# 2_4_0-.net
KiCad netlist of a schematic drawn in Altium Designer
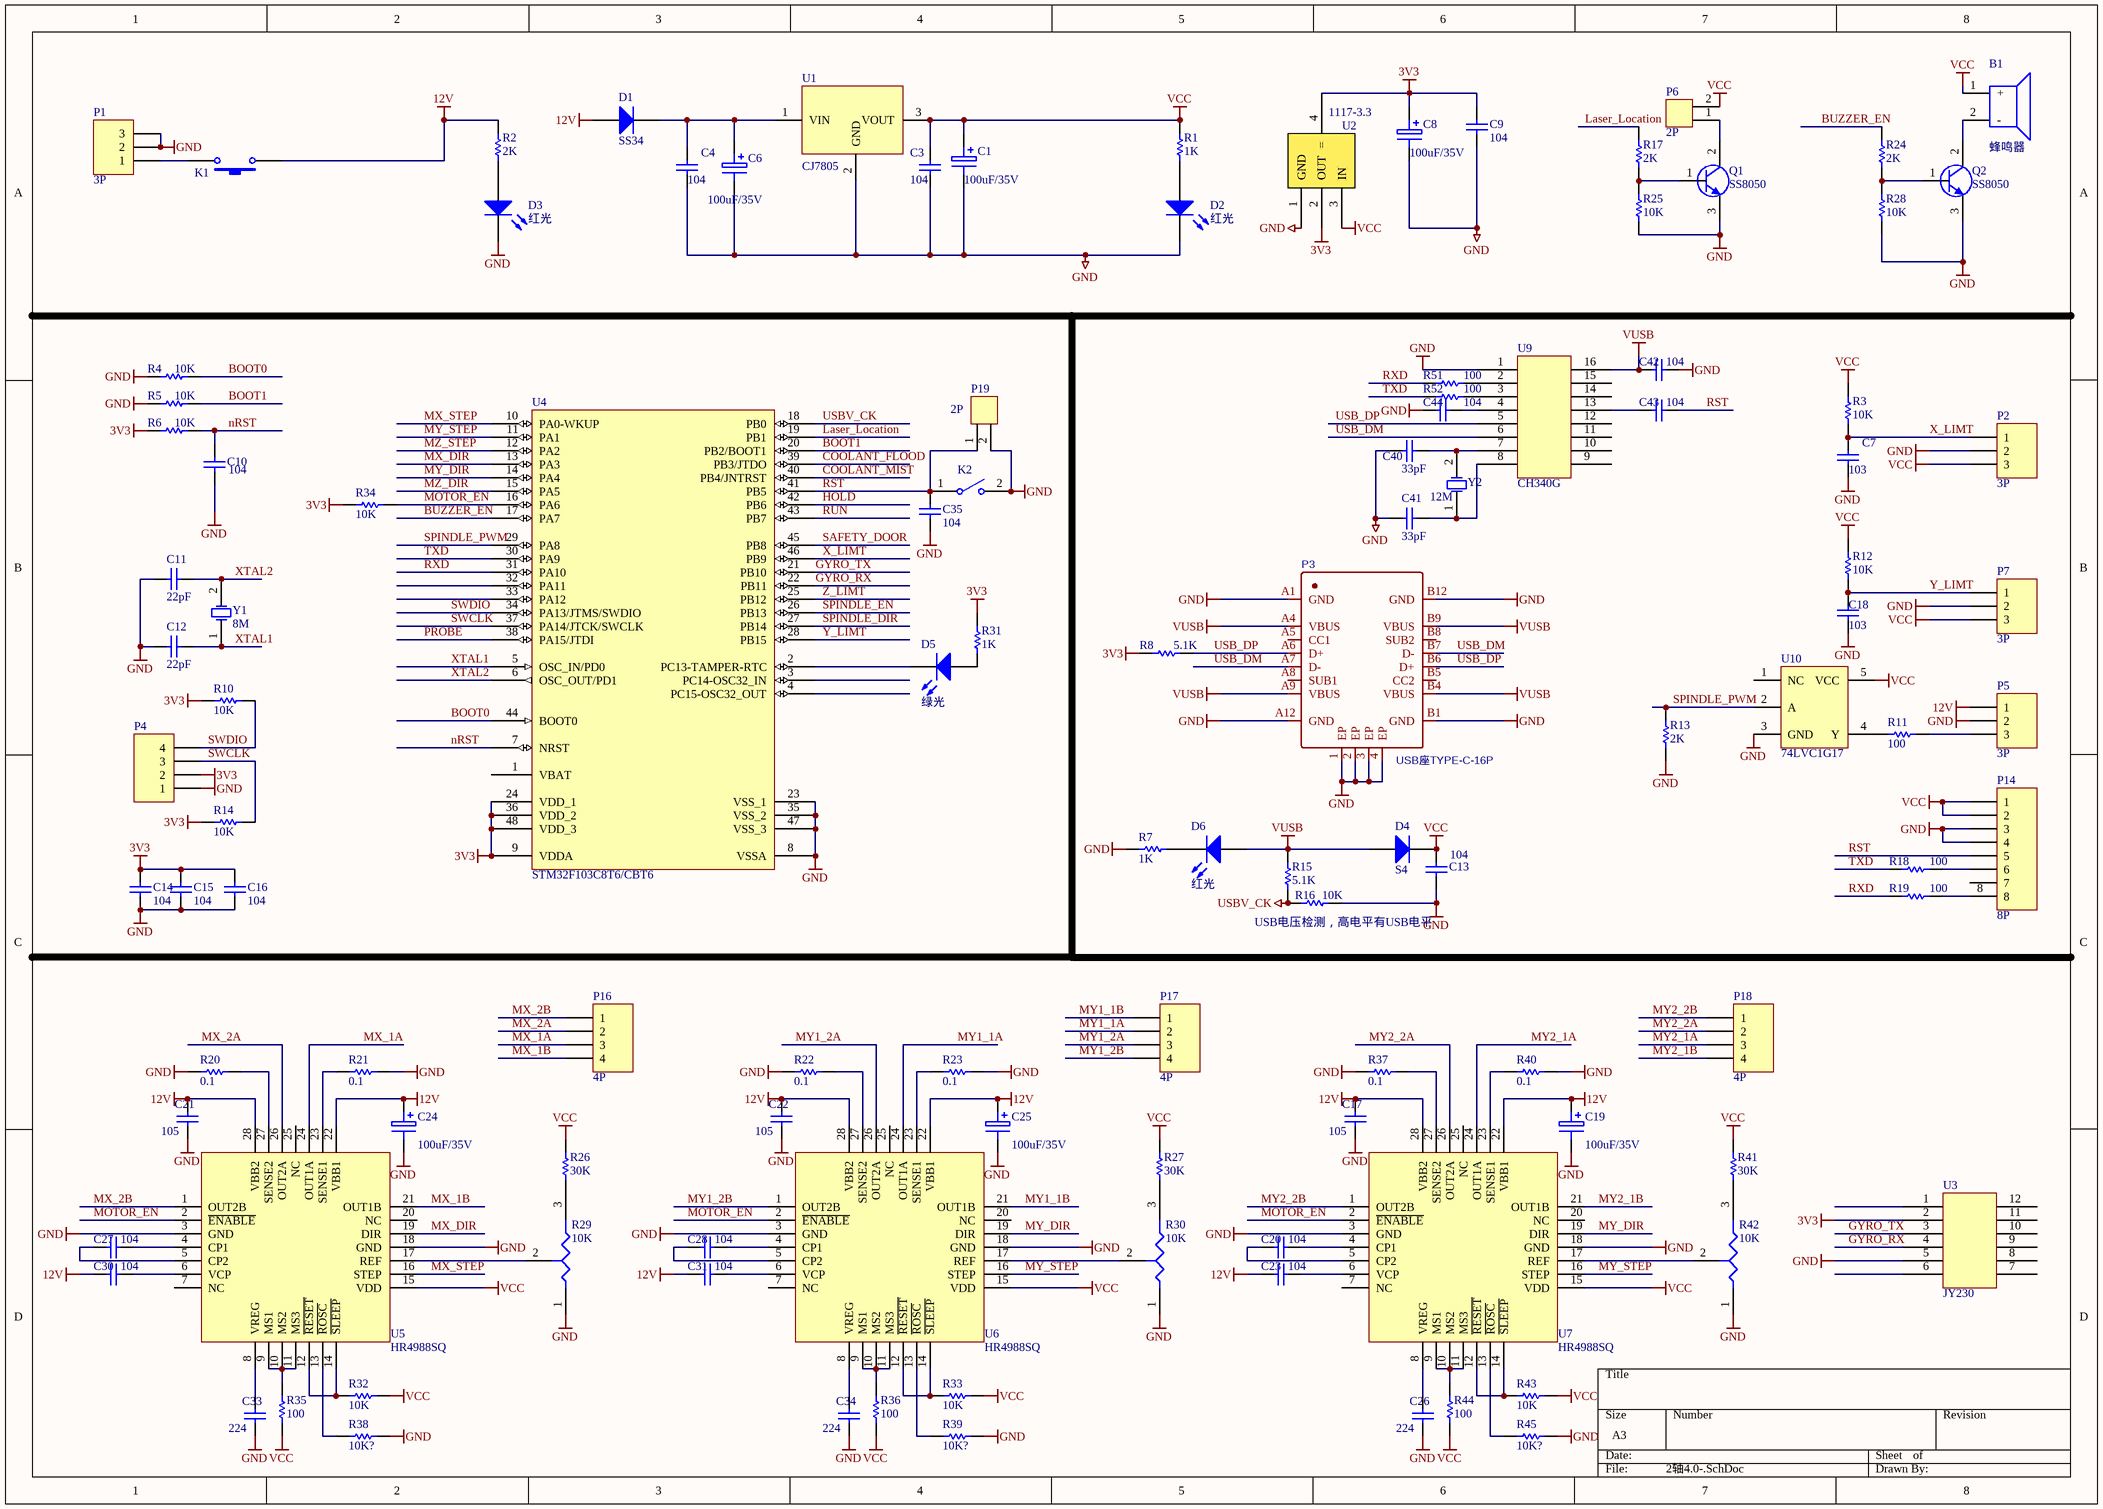
[diagram p0: 2轴4.0-.SchDoc]

(export (version "E")
  (design (tool "Eeschema 10.0.6"))
  (components
    (comp (ref "B1") (value "蜂鸣器") (footprint "蜂鸣器9") (libsource (lib "SCH封装库") (part "蜂鸣器")))
    (comp (ref "C1") (value "100uF/35V") (footprint "电解电容贴片6x6") (libsource (lib "*") (part "ELECTRO1")))
    (comp (ref "C3")
      (value "104")
      (footprint "0603C")
      (description "Capacitor (Semiconductor SIM Model)")
      (fields (field (name "PUBLISHER") "Altium Limited"))
      (libsource (lib "Miscellaneous Devices") (part "Cap Semi"))
    )
    (comp (ref "C4") (value "104") (footprint "0603C") (libsource (lib "SCH封装库") (part "CAP")))
    (comp (ref "C6") (value "100uF/35V") (footprint "电解电容贴片6x6") (libsource (lib "*") (part "ELECTRO1")))
    (comp (ref "C7") (value "103") (footprint "0603C") (libsource (lib "SCH封装库") (part "CAP")))
    (comp (ref "C8") (value "100uF/35V") (footprint "电解电容贴片6x6") (libsource (lib "*") (part "ELECTRO1")))
    (comp (ref "C9")
      (value "104")
      (footprint "0603C")
      (description "Capacitor (Semiconductor SIM Model)")
      (fields (field (name "PUBLISHER") "Altium Limited"))
      (libsource (lib "Miscellaneous Devices") (part "Cap Semi"))
    )
    (comp (ref "C10")
      (value "104")
      (footprint "0603C")
      (description "Capacitor (Semiconductor SIM Model)")
      (fields (field (name "PUBLISHER") "Altium Limited"))
      (libsource (lib "Miscellaneous Devices") (part "Cap Semi"))
    )
    (comp (ref "C11")
      (value "22pF")
      (footprint "0603C")
      (description "Capacitor (Semiconductor SIM Model)")
      (fields (field (name "PUBLISHER") "Altium Limited"))
      (libsource (lib "Miscellaneous Devices") (part "Cap Semi"))
    )
    (comp (ref "C12")
      (value "22pF")
      (footprint "0603C")
      (description "Capacitor (Semiconductor SIM Model)")
      (fields (field (name "PUBLISHER") "Altium Limited"))
      (libsource (lib "Miscellaneous Devices") (part "Cap Semi"))
    )
    (comp (ref "C13")
      (value "104")
      (footprint "0603C")
      (description "Capacitor (Semiconductor SIM Model)")
      (fields (field (name "PUBLISHER") "Altium Limited"))
      (libsource (lib "Miscellaneous Devices") (part "Cap Semi"))
    )
    (comp (ref "C14") (value "104") (footprint "0603C") (libsource (lib "SCH封装库") (part "CAP")))
    (comp (ref "C15") (value "104") (footprint "0603C") (libsource (lib "SCH封装库") (part "CAP")))
    (comp (ref "C16") (value "104") (footprint "0603C") (libsource (lib "SCH封装库") (part "CAP")))
    (comp (ref "C17") (value "105") (footprint "0805C") (libsource (lib "SCH封装库") (part "CAP")))
    (comp (ref "C18") (value "103") (footprint "0603C") (libsource (lib "SCH封装库") (part "CAP")))
    (comp (ref "C19") (value "100uF/35V") (footprint "电解电容贴片6x6") (libsource (lib "*") (part "ELECTRO1")))
    (comp (ref "C20") (value "104") (footprint "0603C") (libsource (lib "SCH封装库") (part "CAP")))
    (comp (ref "C21") (value "105") (footprint "0805C") (libsource (lib "SCH封装库") (part "CAP")))
    (comp (ref "C22") (value "105") (footprint "0805C") (libsource (lib "SCH封装库") (part "CAP")))
    (comp (ref "C23") (value "104") (footprint "0603C") (libsource (lib "SCH封装库") (part "CAP")))
    (comp (ref "C24") (value "100uF/35V") (footprint "电解电容贴片6x6") (libsource (lib "*") (part "ELECTRO1")))
    (comp (ref "C25") (value "100uF/35V") (footprint "电解电容贴片6x6") (libsource (lib "*") (part "ELECTRO1")))
    (comp (ref "C26") (value "224") (footprint "0603C") (libsource (lib "SCH封装库") (part "CAP")))
    (comp (ref "C27") (value "104") (footprint "0603C") (libsource (lib "SCH封装库") (part "CAP")))
    (comp (ref "C28") (value "104") (footprint "0603C") (libsource (lib "SCH封装库") (part "CAP")))
    (comp (ref "C30") (value "104") (footprint "0603C") (libsource (lib "SCH封装库") (part "CAP")))
    (comp (ref "C31") (value "104") (footprint "0603C") (libsource (lib "SCH封装库") (part "CAP")))
    (comp (ref "C33") (value "224") (footprint "0603C") (libsource (lib "SCH封装库") (part "CAP")))
    (comp (ref "C34") (value "224") (footprint "0603C") (libsource (lib "SCH封装库") (part "CAP")))
    (comp (ref "C35")
      (value "104")
      (footprint "0603C")
      (description "Capacitor (Semiconductor SIM Model)")
      (fields (field (name "PUBLISHER") "Altium Limited"))
      (libsource (lib "Miscellaneous Devices") (part "Cap Semi"))
    )
    (comp (ref "C40")
      (value "33pF")
      (footprint "0603C")
      (description "Capacitor (Semiconductor SIM Model)")
      (fields (field (name "PUBLISHER") "Altium Limited"))
      (libsource (lib "Miscellaneous Devices") (part "Cap Semi"))
    )
    (comp (ref "C41")
      (value "33pF")
      (footprint "0603C")
      (description "Capacitor (Semiconductor SIM Model)")
      (fields (field (name "PUBLISHER") "Altium Limited"))
      (libsource (lib "Miscellaneous Devices") (part "Cap Semi"))
    )
    (comp (ref "C42")
      (value "104")
      (footprint "0603C")
      (description "Capacitor (Semiconductor SIM Model)")
      (fields (field (name "PUBLISHER") "Altium Limited"))
      (libsource (lib "Miscellaneous Devices") (part "Cap Semi"))
    )
    (comp (ref "C43")
      (value "104")
      (footprint "0603C")
      (description "Capacitor (Semiconductor SIM Model)")
      (fields (field (name "PUBLISHER") "Altium Limited"))
      (libsource (lib "Miscellaneous Devices") (part "Cap Semi"))
    )
    (comp (ref "C44")
      (value "104")
      (footprint "0603C")
      (description "Capacitor (Semiconductor SIM Model)")
      (fields (field (name "PUBLISHER") "Altium Limited"))
      (libsource (lib "Miscellaneous Devices") (part "Cap Semi"))
    )
    (comp (ref "D1") (value "SS34") (footprint "SMA") (libsource (lib "SCH封装库") (part "1N4148")))
    (comp (ref "D2") (value "红光") (footprint "0603LED") (libsource (lib "SCH封装库") (part "LED")))
    (comp (ref "D3") (value "红光") (footprint "0603LED") (libsource (lib "SCH封装库") (part "LED")))
    (comp (ref "D4") (value "S4") (footprint "SOD-123") (libsource (lib "SCH封装库") (part "1N4148")))
    (comp (ref "D5") (value "绿光") (footprint "0603LED") (libsource (lib "SCH封装库") (part "LED")))
    (comp (ref "D6") (value "红光") (footprint "0603LED") (libsource (lib "SCH封装库") (part "LED")))
    (comp (ref "K1") (value "按键") (footprint "按键18x13") (libsource (lib "SCH封装库") (part "按键")))
    (comp (ref "K2") (value "开关") (footprint "按键6x6贴片") (libsource (lib "SCH封装库") (part "开关")))
    (comp (ref "P1") (value "3P") (footprint "DC0044A") (libsource (lib "") (part "3P_1")))
    (comp (ref "P2") (value "3P") (footprint "HDR1X3_P") (libsource (lib "SCH封装库") (part "3P")))
    (comp (ref "P3")
      (value "USB座TYPE-C-16P")
      (footprint "USB-TYPE-C-16P")
      (fields
        (field (name "BOM_SUPPLIER PART") "C709358")
        (field (name "BOM_MANUFACTURER PART") "KH-TYPE-C-16P-T")
        (field (name "CONTRIBUTOR") "LCSC")
      )
      (libsource (lib "SCH封装库") (part "USB座TYPE-C-16P"))
    )
    (comp (ref "P4") (value "~") (footprint "SIP4") (libsource (lib "") (part "4P_1")))
    (comp (ref "P5") (value "3P") (footprint "HDR1X3_P") (libsource (lib "SCH封装库") (part "3P")))
    (comp (ref "P6") (value "2P") (footprint "HDR1X2_P") (libsource (lib "SCH封装库") (part "2P")))
    (comp (ref "P7") (value "3P") (footprint "HDR1X3_P") (libsource (lib "SCH封装库") (part "3P")))
    (comp (ref "P14") (value "8P") (footprint "IDC8弯脚") (libsource (lib "SCH封装库") (part "8P")))
    (comp (ref "P16") (value "4P") (footprint "HDR1X4_P") (libsource (lib "SCH封装库") (part "4P")))
    (comp (ref "P17") (value "4P") (footprint "HDR1X4_P") (libsource (lib "SCH封装库") (part "4P")))
    (comp (ref "P18") (value "4P") (footprint "HDR1X4_P") (libsource (lib "SCH封装库") (part "4P")))
    (comp (ref "P19") (value "2P") (footprint "HDR1X2_P") (libsource (lib "") (part "2P_1")))
    (comp (ref "Q1")
      (value "SS8050")
      (footprint "SOT-23")
      (fields (field (name "PUBLISHER") "Altium Limited"))
      (libsource (lib "SCH封装库") (part "NPN"))
    )
    (comp (ref "Q2")
      (value "SS8050")
      (footprint "SOT-23")
      (fields (field (name "PUBLISHER") "Altium Limited"))
      (libsource (lib "SCH封装库") (part "NPN"))
    )
    (comp (ref "R1")
      (value "1K")
      (footprint "0603R")
      (description "Resistor")
      (fields (field (name "PUBLISHER") "Altium Limited"))
      (libsource (lib "SCH封装库") (part "RES"))
    )
    (comp (ref "R2")
      (value "2K")
      (footprint "0603R")
      (description "Resistor")
      (fields (field (name "PUBLISHER") "Altium Limited"))
      (libsource (lib "SCH封装库") (part "RES"))
    )
    (comp (ref "R3")
      (value "10K")
      (footprint "0603R")
      (description "Resistor")
      (fields (field (name "PUBLISHER") "Altium Limited"))
      (libsource (lib "SCH封装库") (part "RES"))
    )
    (comp (ref "R4")
      (value "10K")
      (footprint "0603R")
      (description "Resistor")
      (fields (field (name "Comment") "10k") (field (name "PUBLISHER") "Altium Limited"))
      (libsource (lib "SCH封装库") (part "RES"))
    )
    (comp (ref "R5")
      (value "10K")
      (footprint "0603R")
      (description "Resistor")
      (fields (field (name "Comment") "10k") (field (name "PUBLISHER") "Altium Limited"))
      (libsource (lib "SCH封装库") (part "RES"))
    )
    (comp (ref "R6")
      (value "10K")
      (footprint "0603R")
      (description "Resistor")
      (fields (field (name "Comment") "10k") (field (name "PUBLISHER") "Altium Limited"))
      (libsource (lib "SCH封装库") (part "RES"))
    )
    (comp (ref "R7")
      (value "1K")
      (footprint "0603R")
      (description "Resistor")
      (fields (field (name "PUBLISHER") "Altium Limited"))
      (libsource (lib "SCH封装库") (part "RES"))
    )
    (comp (ref "R8")
      (value "5.1K")
      (footprint "0603R")
      (description "Resistor")
      (fields (field (name "PUBLISHER") "Altium Limited"))
      (libsource (lib "SCH封装库") (part "RES"))
    )
    (comp (ref "R10")
      (value "10K")
      (footprint "0603R")
      (description "Resistor")
      (fields (field (name "Comment") "10k") (field (name "PUBLISHER") "Altium Limited"))
      (libsource (lib "SCH封装库") (part "RES"))
    )
    (comp (ref "R11")
      (value "100")
      (footprint "0603R")
      (description "Resistor")
      (fields (field (name "PUBLISHER") "Altium Limited"))
      (libsource (lib "SCH封装库") (part "RES"))
    )
    (comp (ref "R12")
      (value "10K")
      (footprint "0603R")
      (description "Resistor")
      (fields (field (name "PUBLISHER") "Altium Limited"))
      (libsource (lib "SCH封装库") (part "RES"))
    )
    (comp (ref "R13")
      (value "2K")
      (footprint "0603R")
      (description "Resistor")
      (fields (field (name "PUBLISHER") "Altium Limited"))
      (libsource (lib "SCH封装库") (part "RES"))
    )
    (comp (ref "R14")
      (value "10K")
      (footprint "0603R")
      (description "Resistor")
      (fields (field (name "Comment") "10k") (field (name "PUBLISHER") "Altium Limited"))
      (libsource (lib "SCH封装库") (part "RES"))
    )
    (comp (ref "R15")
      (value "5.1K")
      (footprint "0603R")
      (description "Resistor")
      (fields (field (name "PUBLISHER") "Altium Limited"))
      (libsource (lib "SCH封装库") (part "RES"))
    )
    (comp (ref "R16")
      (value "10K")
      (footprint "0603R")
      (description "Resistor")
      (fields (field (name "PUBLISHER") "Altium Limited"))
      (libsource (lib "SCH封装库") (part "RES"))
    )
    (comp (ref "R17")
      (value "2K")
      (footprint "0603R")
      (description "Resistor")
      (fields (field (name "PUBLISHER") "Altium Limited"))
      (libsource (lib "SCH封装库") (part "RES"))
    )
    (comp (ref "R18")
      (value "100")
      (footprint "0603R")
      (description "Resistor")
      (fields (field (name "PUBLISHER") "Altium Limited"))
      (libsource (lib "SCH封装库") (part "RES"))
    )
    (comp (ref "R19")
      (value "100")
      (footprint "0603R")
      (description "Resistor")
      (fields (field (name "PUBLISHER") "Altium Limited"))
      (libsource (lib "SCH封装库") (part "RES"))
    )
    (comp (ref "R20")
      (value "0.1")
      (footprint "0805R")
      (description "Resistor")
      (fields (field (name "PUBLISHER") "Altium Limited"))
      (libsource (lib "SCH封装库") (part "RES"))
    )
    (comp (ref "R21")
      (value "0.1")
      (footprint "0805R")
      (description "Resistor")
      (fields (field (name "PUBLISHER") "Altium Limited"))
      (libsource (lib "SCH封装库") (part "RES"))
    )
    (comp (ref "R22")
      (value "0.1")
      (footprint "0805R")
      (description "Resistor")
      (fields (field (name "PUBLISHER") "Altium Limited"))
      (libsource (lib "SCH封装库") (part "RES"))
    )
    (comp (ref "R23")
      (value "0.1")
      (footprint "0805R")
      (description "Resistor")
      (fields (field (name "PUBLISHER") "Altium Limited"))
      (libsource (lib "SCH封装库") (part "RES"))
    )
    (comp (ref "R24")
      (value "2K")
      (footprint "0603R")
      (description "Resistor")
      (fields (field (name "PUBLISHER") "Altium Limited"))
      (libsource (lib "SCH封装库") (part "RES"))
    )
    (comp (ref "R25")
      (value "10K")
      (footprint "0603R")
      (description "Resistor")
      (fields (field (name "PUBLISHER") "Altium Limited"))
      (libsource (lib "SCH封装库") (part "RES"))
    )
    (comp (ref "R26")
      (value "30K")
      (footprint "0603R")
      (description "Resistor")
      (fields (field (name "PUBLISHER") "Altium Limited"))
      (libsource (lib "SCH封装库") (part "RES"))
    )
    (comp (ref "R27")
      (value "30K")
      (footprint "0603R")
      (description "Resistor")
      (fields (field (name "PUBLISHER") "Altium Limited"))
      (libsource (lib "SCH封装库") (part "RES"))
    )
    (comp (ref "R28")
      (value "10K")
      (footprint "0603R")
      (description "Resistor")
      (fields (field (name "PUBLISHER") "Altium Limited"))
      (libsource (lib "SCH封装库") (part "RES"))
    )
    (comp (ref "R29") (value "10K") (footprint "松下贴片电位器3x3") (libsource (lib "SCH封装库") (part "电位器")))
    (comp (ref "R30") (value "10K") (footprint "松下贴片电位器3x3") (libsource (lib "SCH封装库") (part "电位器")))
    (comp (ref "R31")
      (value "1K")
      (footprint "0603R")
      (description "Resistor")
      (fields (field (name "PUBLISHER") "Altium Limited"))
      (libsource (lib "SCH封装库") (part "RES"))
    )
    (comp (ref "R32")
      (value "10K")
      (footprint "0603R")
      (description "Resistor")
      (fields (field (name "PUBLISHER") "Altium Limited"))
      (libsource (lib "SCH封装库") (part "RES"))
    )
    (comp (ref "R33")
      (value "10K")
      (footprint "0603R")
      (description "Resistor")
      (fields (field (name "PUBLISHER") "Altium Limited"))
      (libsource (lib "SCH封装库") (part "RES"))
    )
    (comp (ref "R34")
      (value "10K")
      (footprint "0603R")
      (description "Resistor")
      (fields (field (name "PUBLISHER") "Altium Limited"))
      (libsource (lib "SCH封装库") (part "RES"))
    )
    (comp (ref "R35")
      (value "100")
      (footprint "0603R")
      (description "Resistor")
      (fields (field (name "PUBLISHER") "Altium Limited"))
      (libsource (lib "SCH封装库") (part "RES"))
    )
    (comp (ref "R36")
      (value "100")
      (footprint "0603R")
      (description "Resistor")
      (fields (field (name "PUBLISHER") "Altium Limited"))
      (libsource (lib "SCH封装库") (part "RES"))
    )
    (comp (ref "R37")
      (value "0.1")
      (footprint "0805R")
      (description "Resistor")
      (fields (field (name "PUBLISHER") "Altium Limited"))
      (libsource (lib "SCH封装库") (part "RES"))
    )
    (comp (ref "R38")
      (value "10K?")
      (footprint "0603R")
      (description "Resistor")
      (fields (field (name "PUBLISHER") "Altium Limited"))
      (libsource (lib "SCH封装库") (part "RES"))
    )
    (comp (ref "R39")
      (value "10K?")
      (footprint "0603R")
      (description "Resistor")
      (fields (field (name "PUBLISHER") "Altium Limited"))
      (libsource (lib "SCH封装库") (part "RES"))
    )
    (comp (ref "R40")
      (value "0.1")
      (footprint "0805R")
      (description "Resistor")
      (fields (field (name "PUBLISHER") "Altium Limited"))
      (libsource (lib "SCH封装库") (part "RES"))
    )
    (comp (ref "R41")
      (value "30K")
      (footprint "0603R")
      (description "Resistor")
      (fields (field (name "PUBLISHER") "Altium Limited"))
      (libsource (lib "SCH封装库") (part "RES"))
    )
    (comp (ref "R42") (value "10K") (footprint "松下贴片电位器3x3") (libsource (lib "SCH封装库") (part "电位器")))
    (comp (ref "R43")
      (value "10K")
      (footprint "0603R")
      (description "Resistor")
      (fields (field (name "PUBLISHER") "Altium Limited"))
      (libsource (lib "SCH封装库") (part "RES"))
    )
    (comp (ref "R44")
      (value "100")
      (footprint "0603R")
      (description "Resistor")
      (fields (field (name "PUBLISHER") "Altium Limited"))
      (libsource (lib "SCH封装库") (part "RES"))
    )
    (comp (ref "R45")
      (value "10K?")
      (footprint "0603R")
      (description "Resistor")
      (fields (field (name "PUBLISHER") "Altium Limited"))
      (libsource (lib "SCH封装库") (part "RES"))
    )
    (comp (ref "R51")
      (value "100")
      (footprint "0603R")
      (description "Resistor")
      (fields (field (name "PUBLISHER") "Altium Limited"))
      (libsource (lib "SCH封装库") (part "RES"))
    )
    (comp (ref "R52")
      (value "100")
      (footprint "0603R")
      (description "Resistor")
      (fields (field (name "PUBLISHER") "Altium Limited"))
      (libsource (lib "SCH封装库") (part "RES"))
    )
    (comp (ref "U1") (value "CJ7805") (footprint "TO-263-2") (libsource (lib "SCH封装库") (part "7805")))
    (comp (ref "U2") (value "1117-3.3") (footprint "SOT-223") (libsource (lib "Party600") (part "LM1117")))
    (comp (ref "U3") (value "JY230") (footprint "舵螺仪JY-230") (libsource (lib "SCH封装库") (part "DIP12")))
    (comp (ref "U4")
      (value "STM32F103C8T6/CBT6")
      (footprint "LQFP48")
      (description "STM32 ARM-based 32-bit MCU with 32 Kbytes Flash, 48-pin LQFP, Industrial Temperature")
      (fields (field (name "PUBLISHER") "*"))
      (libsource (lib "ST Microcontroller 32-Bit STM32 SCH") (part "STM32F103C6T6"))
    )
    (comp (ref "U5") (value "HR4988SQ") (footprint "QFN28") (libsource (lib "SCH封装库") (part "HR4988")))
    (comp (ref "U6") (value "HR4988SQ") (footprint "QFN28") (libsource (lib "SCH封装库") (part "HR4988")))
    (comp (ref "U7") (value "HR4988SQ") (footprint "QFN28") (libsource (lib "SCH封装库") (part "HR4988")))
    (comp (ref "U9") (value "CH340G") (footprint "SOP16") (libsource (lib "SCH封装库") (part "DIP16")))
    (comp (ref "U10")
      (value "74LVC1G17")
      (footprint "SOT-23-5")
      (libsource (lib "SCH封装库") (part "74LVC1G17"))
    )
    (comp (ref "Y1")
      (value "8M")
      (footprint "晶振贴片")
      (description "Crystal Oscillator")
      (fields (field (name "PUBLISHER") "Altium Limited"))
      (libsource (lib "Miscellaneous Devices") (part "XTAL"))
    )
    (comp (ref "Y2")
      (value "12M")
      (footprint "晶振贴片49SSMD")
      (description "Crystal Oscillator")
      (fields (field (name "PUBLISHER") "Altium Limited"))
      (libsource (lib "Miscellaneous Devices") (part "XTAL"))
    )
  )
  (nets
    (net (code "1") (name "/BOOT0") (class "Default")
      (node (ref "R4") (pin "2") (pinfunction "2_2") (pintype "passive"))
      (node (ref "U4") (pin "44") (pinfunction "BOOT0_44") (pintype "input"))
    )
    (net (code "2") (name "/BOOT1") (class "Default")
      (node (ref "R5") (pin "2") (pinfunction "2_2") (pintype "passive"))
      (node (ref "U4") (pin "20") (pinfunction "PB2/BOOT1_20") (pintype "bidirectional"))
    )
    (net (code "3") (name "/BUZZER_EN") (class "Default")
      (node (ref "R24") (pin "1") (pinfunction "1_1") (pintype "passive"))
      (node (ref "U4") (pin "17") (pinfunction "PA7_17") (pintype "bidirectional"))
    )
    (net (code "4") (name "/COOLANT_FLOOD") (class "Default")
      (node (ref "U4") (pin "39") (pinfunction "PB3/JTDO_39") (pintype "bidirectional"))
    )
    (net (code "5") (name "/COOLANT_MIST") (class "Default")
      (node (ref "U4") (pin "40") (pinfunction "PB4/JNTRST_40") (pintype "bidirectional"))
    )
    (net (code "6") (name "/GYRO_RX") (class "Default")
      (node (ref "U3") (pin "4") (pinfunction "4_4") (pintype "passive"))
      (node (ref "U4") (pin "22") (pinfunction "PB11_22") (pintype "bidirectional"))
    )
    (net (code "7") (name "/GYRO_TX") (class "Default")
      (node (ref "U3") (pin "3") (pinfunction "3_3") (pintype "passive"))
      (node (ref "U4") (pin "21") (pinfunction "PB10_21") (pintype "bidirectional"))
    )
    (net (code "8") (name "/HOLD") (class "Default")
      (node (ref "U4") (pin "42") (pinfunction "PB6_42") (pintype "bidirectional"))
    )
    (net (code "9") (name "/Laser_Location") (class "Default")
      (node (ref "R17") (pin "1") (pinfunction "1_1") (pintype "passive"))
      (node (ref "U4") (pin "19") (pinfunction "PB1_19") (pintype "bidirectional"))
    )
    (net (code "10") (name "/MOTOR_EN") (class "Default")
      (node (ref "R34") (pin "1") (pinfunction "1_1") (pintype "passive"))
      (node (ref "U4") (pin "16") (pinfunction "PA6_16") (pintype "bidirectional"))
      (node (ref "U5") (pin "2") (pinfunction "~{ENABLE}_2") (pintype "passive"))
      (node (ref "U6") (pin "2") (pinfunction "~{ENABLE}_2") (pintype "passive"))
      (node (ref "U7") (pin "2") (pinfunction "~{ENABLE}_2") (pintype "passive"))
    )
    (net (code "11") (name "/MX_1A") (class "Default")
      (node (ref "P16") (pin "3") (pinfunction "3_3") (pintype "passive"))
      (node (ref "U5") (pin "24") (pinfunction "OUT1A_24") (pintype "passive"))
    )
    (net (code "12") (name "/MX_1B") (class "Default")
      (node (ref "P16") (pin "4") (pinfunction "4_4") (pintype "passive"))
      (node (ref "U5") (pin "21") (pinfunction "OUT1B_21") (pintype "passive"))
    )
    (net (code "13") (name "/MX_2A") (class "Default")
      (node (ref "P16") (pin "2") (pinfunction "2_2") (pintype "passive"))
      (node (ref "U5") (pin "26") (pinfunction "OUT2A_26") (pintype "passive"))
    )
    (net (code "14") (name "/MX_2B") (class "Default")
      (node (ref "P16") (pin "1") (pinfunction "1_1") (pintype "passive"))
      (node (ref "U5") (pin "1") (pinfunction "OUT2B_1") (pintype "passive"))
    )
    (net (code "15") (name "/MX_DIR") (class "Default")
      (node (ref "U4") (pin "13") (pinfunction "PA3_13") (pintype "bidirectional"))
      (node (ref "U5") (pin "19") (pinfunction "DIR_19") (pintype "passive"))
    )
    (net (code "16") (name "/MX_STEP") (class "Default")
      (node (ref "U4") (pin "10") (pinfunction "PA0-WKUP_10") (pintype "bidirectional"))
      (node (ref "U5") (pin "16") (pinfunction "STEP_16") (pintype "passive"))
    )
    (net (code "17") (name "/MY1_1A") (class "Default")
      (node (ref "P17") (pin "2") (pinfunction "2_2") (pintype "passive"))
      (node (ref "U6") (pin "24") (pinfunction "OUT1A_24") (pintype "passive"))
    )
    (net (code "18") (name "/MY1_1B") (class "Default")
      (node (ref "P17") (pin "1") (pinfunction "1_1") (pintype "passive"))
      (node (ref "U6") (pin "21") (pinfunction "OUT1B_21") (pintype "passive"))
    )
    (net (code "19") (name "/MY1_2A") (class "Default")
      (node (ref "P17") (pin "3") (pinfunction "3_3") (pintype "passive"))
      (node (ref "U6") (pin "26") (pinfunction "OUT2A_26") (pintype "passive"))
    )
    (net (code "20") (name "/MY1_2B") (class "Default")
      (node (ref "P17") (pin "4") (pinfunction "4_4") (pintype "passive"))
      (node (ref "U6") (pin "1") (pinfunction "OUT2B_1") (pintype "passive"))
    )
    (net (code "21") (name "/MY2_1A") (class "Default")
      (node (ref "P18") (pin "3") (pinfunction "3_3") (pintype "passive"))
      (node (ref "U7") (pin "24") (pinfunction "OUT1A_24") (pintype "passive"))
    )
    (net (code "22") (name "/MY2_1B") (class "Default")
      (node (ref "P18") (pin "4") (pinfunction "4_4") (pintype "passive"))
      (node (ref "U7") (pin "21") (pinfunction "OUT1B_21") (pintype "passive"))
    )
    (net (code "23") (name "/MY2_2A") (class "Default")
      (node (ref "P18") (pin "2") (pinfunction "2_2") (pintype "passive"))
      (node (ref "U7") (pin "26") (pinfunction "OUT2A_26") (pintype "passive"))
    )
    (net (code "24") (name "/MY2_2B") (class "Default")
      (node (ref "P18") (pin "1") (pinfunction "1_1") (pintype "passive"))
      (node (ref "U7") (pin "1") (pinfunction "OUT2B_1") (pintype "passive"))
    )
    (net (code "25") (name "/MY_DIR") (class "Default")
      (node (ref "U4") (pin "14") (pinfunction "PA4_14") (pintype "bidirectional"))
      (node (ref "U6") (pin "19") (pinfunction "DIR_19") (pintype "passive"))
      (node (ref "U7") (pin "19") (pinfunction "DIR_19") (pintype "passive"))
    )
    (net (code "26") (name "/MY_STEP") (class "Default")
      (node (ref "U4") (pin "11") (pinfunction "PA1_11") (pintype "bidirectional"))
      (node (ref "U6") (pin "16") (pinfunction "STEP_16") (pintype "passive"))
      (node (ref "U7") (pin "16") (pinfunction "STEP_16") (pintype "passive"))
    )
    (net (code "27") (name "/MZ_DIR") (class "Default")
      (node (ref "U4") (pin "15") (pinfunction "PA5_15") (pintype "bidirectional"))
    )
    (net (code "28") (name "/MZ_STEP") (class "Default")
      (node (ref "U4") (pin "12") (pinfunction "PA2_12") (pintype "bidirectional"))
    )
    (net (code "29") (name "/PROBE") (class "Default")
      (node (ref "U4") (pin "38") (pinfunction "PA15/JTDI_38") (pintype "bidirectional"))
    )
    (net (code "30") (name "/RST") (class "Default")
      (node (ref "C35") (pin "1") (pinfunction "1_1") (pintype "passive"))
      (node (ref "C43") (pin "2") (pinfunction "2_2") (pintype "passive"))
      (node (ref "K2") (pin "1") (pinfunction "COMMON_1") (pintype "passive"))
      (node (ref "P14") (pin "5") (pinfunction "5_5") (pintype "passive"))
      (node (ref "P19") (pin "1") (pintype "passive"))
      (node (ref "U4") (pin "41") (pinfunction "PB5_41") (pintype "bidirectional"))
    )
    (net (code "31") (name "/RUN") (class "Default")
      (node (ref "U4") (pin "43") (pinfunction "PB7_43") (pintype "bidirectional"))
    )
    (net (code "32") (name "/RXD") (class "Default")
      (node (ref "R19") (pin "1") (pinfunction "1_1") (pintype "passive"))
      (node (ref "R51") (pin "2") (pinfunction "2_2") (pintype "passive"))
      (node (ref "U4") (pin "31") (pinfunction "PA10_31") (pintype "bidirectional"))
    )
    (net (code "33") (name "/SAFETY_DOOR") (class "Default")
      (node (ref "U4") (pin "45") (pinfunction "PB8_45") (pintype "bidirectional"))
    )
    (net (code "34") (name "/SPINDLE_DIR") (class "Default")
      (node (ref "U4") (pin "27") (pinfunction "PB14_27") (pintype "bidirectional"))
    )
    (net (code "35") (name "/SPINDLE_EN") (class "Default")
      (node (ref "U4") (pin "26") (pinfunction "PB13_26") (pintype "bidirectional"))
    )
    (net (code "36") (name "/SPINDLE_PWM") (class "Default")
      (node (ref "R13") (pin "2") (pinfunction "2_2") (pintype "passive"))
      (node (ref "U10") (pin "2") (pinfunction "A_2") (pintype "passive"))
      (node (ref "U4") (pin "29") (pinfunction "PA8_29") (pintype "bidirectional"))
    )
    (net (code "37") (name "/SWCLK") (class "Default")
      (node (ref "P4") (pin "3") (pinfunction "3_3") (pintype "passive"))
      (node (ref "R14") (pin "1") (pinfunction "1_1") (pintype "passive"))
      (node (ref "U4") (pin "37") (pinfunction "PA14/JTCK/SWCLK_37") (pintype "bidirectional"))
    )
    (net (code "38") (name "/SWDIO") (class "Default")
      (node (ref "P4") (pin "4") (pinfunction "4_4") (pintype "passive"))
      (node (ref "R10") (pin "1") (pinfunction "1_1") (pintype "passive"))
      (node (ref "U4") (pin "34") (pinfunction "PA13/JTMS/SWDIO_34") (pintype "bidirectional"))
    )
    (net (code "39") (name "/TXD") (class "Default")
      (node (ref "R18") (pin "1") (pinfunction "1_1") (pintype "passive"))
      (node (ref "R52") (pin "2") (pinfunction "2_2") (pintype "passive"))
      (node (ref "U4") (pin "30") (pinfunction "PA9_30") (pintype "bidirectional"))
    )
    (net (code "40") (name "/USB_DM") (class "Default")
      (node (ref "P3") (pin "A7") (pinfunction "D-_A7") (pintype "passive"))
      (node (ref "P3") (pin "B7") (pinfunction "D-_B7") (pintype "passive"))
      (node (ref "U9") (pin "6") (pinfunction "6_6") (pintype "passive"))
    )
    (net (code "41") (name "/USB_DP") (class "Default")
      (node (ref "P3") (pin "A6") (pinfunction "D+_A6") (pintype "passive"))
      (node (ref "P3") (pin "B6") (pinfunction "D+_B6") (pintype "passive"))
      (node (ref "R8") (pin "2") (pinfunction "2_2") (pintype "passive"))
      (node (ref "U9") (pin "5") (pinfunction "5_5") (pintype "passive"))
    )
    (net (code "42") (name "/XTAL1") (class "Default")
      (node (ref "C12") (pin "1") (pinfunction "1_1") (pintype "passive"))
      (node (ref "U4") (pin "5") (pinfunction "OSC_IN/PD0_5") (pintype "input"))
      (node (ref "Y1") (pin "1") (pinfunction "OSC1_1") (pintype "passive"))
    )
    (net (code "43") (name "/XTAL2") (class "Default")
      (node (ref "C11") (pin "1") (pinfunction "1_1") (pintype "passive"))
      (node (ref "U4") (pin "6") (pinfunction "OSC_OUT/PD1_6") (pintype "output"))
      (node (ref "Y1") (pin "2") (pinfunction "OSC2_2") (pintype "passive"))
    )
    (net (code "44") (name "/X_LIMT") (class "Default")
      (node (ref "C7") (pin "2") (pinfunction "2_2") (pintype "passive"))
      (node (ref "P2") (pin "1") (pinfunction "1_1") (pintype "passive"))
      (node (ref "R3") (pin "1") (pinfunction "1_1") (pintype "passive"))
      (node (ref "U4") (pin "46") (pinfunction "PB9_46") (pintype "bidirectional"))
    )
    (net (code "45") (name "/Y_LIMT") (class "Default")
      (node (ref "C18") (pin "2") (pinfunction "2_2") (pintype "passive"))
      (node (ref "P7") (pin "1") (pinfunction "1_1") (pintype "passive"))
      (node (ref "R12") (pin "1") (pinfunction "1_1") (pintype "passive"))
      (node (ref "U4") (pin "28") (pinfunction "PB15_28") (pintype "bidirectional"))
    )
    (net (code "46") (name "/Z_LIMT") (class "Default")
      (node (ref "U4") (pin "25") (pinfunction "PB12_25") (pintype "bidirectional"))
    )
    (net (code "47") (name "/nRST") (class "Default")
      (node (ref "C10") (pin "2") (pinfunction "2_2") (pintype "passive"))
      (node (ref "R6") (pin "2") (pinfunction "2_2") (pintype "passive"))
      (node (ref "U4") (pin "7") (pinfunction "NRST_7") (pintype "bidirectional"))
    )
    (net (code "48") (name "3V3") (class "Default")
      (node (ref "C14") (pin "2") (pinfunction "2_2") (pintype "passive"))
      (node (ref "C15") (pin "2") (pinfunction "2_2") (pintype "passive"))
      (node (ref "C16") (pin "2") (pinfunction "2_2") (pintype "passive"))
      (node (ref "C8") (pin "1") (pintype "passive"))
      (node (ref "C9") (pin "2") (pinfunction "2_2") (pintype "passive"))
      (node (ref "P4") (pin "2") (pinfunction "2_2") (pintype "passive"))
      (node (ref "R10") (pin "2") (pinfunction "2_2") (pintype "passive"))
      (node (ref "R14") (pin "2") (pinfunction "2_2") (pintype "passive"))
      (node (ref "R31") (pin "2") (pinfunction "2_2") (pintype "passive"))
      (node (ref "R34") (pin "2") (pinfunction "2_2") (pintype "passive"))
      (node (ref "R6") (pin "1") (pinfunction "1_1") (pintype "passive"))
      (node (ref "R8") (pin "1") (pinfunction "1_1") (pintype "passive"))
      (node (ref "U2") (pin "2") (pinfunction "OUT_2") (pintype "power_in"))
      (node (ref "U2") (pin "4") (pinfunction "=_4") (pintype "power_in"))
      (node (ref "U3") (pin "2") (pinfunction "2_2") (pintype "passive"))
      (node (ref "U4") (pin "24") (pinfunction "VDD_1_24") (pintype "power_in"))
      (node (ref "U4") (pin "36") (pinfunction "VDD_2_36") (pintype "power_in"))
      (node (ref "U4") (pin "48") (pinfunction "VDD_3_48") (pintype "power_in"))
      (node (ref "U4") (pin "9") (pinfunction "VDDA_9") (pintype "power_in"))
    )
    (net (code "49") (name "12V") (class "Default")
      (node (ref "C17") (pin "1") (pinfunction "1_1") (pintype "passive"))
      (node (ref "C19") (pin "1") (pintype "passive"))
      (node (ref "C21") (pin "1") (pinfunction "1_1") (pintype "passive"))
      (node (ref "C22") (pin "1") (pinfunction "1_1") (pintype "passive"))
      (node (ref "C23") (pin "2") (pinfunction "2_2") (pintype "passive"))
      (node (ref "C24") (pin "1") (pintype "passive"))
      (node (ref "C25") (pin "1") (pintype "passive"))
      (node (ref "C30") (pin "2") (pinfunction "2_2") (pintype "passive"))
      (node (ref "C31") (pin "2") (pinfunction "2_2") (pintype "passive"))
      (node (ref "D1") (pin "1") (pinfunction "1_1") (pintype "passive"))
      (node (ref "K1") (pin "1") (pinfunction "1_1") (pintype "passive"))
      (node (ref "P5") (pin "1") (pinfunction "1_1") (pintype "passive"))
      (node (ref "R2") (pin "1") (pinfunction "1_1") (pintype "passive"))
      (node (ref "U5") (pin "22") (pinfunction "VBB1_22") (pintype "passive"))
      (node (ref "U5") (pin "28") (pinfunction "VBB2_28") (pintype "passive"))
      (node (ref "U6") (pin "22") (pinfunction "VBB1_22") (pintype "passive"))
      (node (ref "U6") (pin "28") (pinfunction "VBB2_28") (pintype "passive"))
      (node (ref "U7") (pin "22") (pinfunction "VBB1_22") (pintype "passive"))
      (node (ref "U7") (pin "28") (pinfunction "VBB2_28") (pintype "passive"))
    )
    (net (code "50") (name "GND") (class "Default")
      (node (ref "C1") (pin "2") (pintype "passive"))
      (node (ref "C10") (pin "1") (pinfunction "1_1") (pintype "passive"))
      (node (ref "C11") (pin "2") (pinfunction "2_2") (pintype "passive"))
      (node (ref "C12") (pin "2") (pinfunction "2_2") (pintype "passive"))
      (node (ref "C13") (pin "1") (pinfunction "1_1") (pintype "passive"))
      (node (ref "C14") (pin "1") (pinfunction "1_1") (pintype "passive"))
      (node (ref "C15") (pin "1") (pinfunction "1_1") (pintype "passive"))
      (node (ref "C16") (pin "1") (pinfunction "1_1") (pintype "passive"))
      (node (ref "C17") (pin "2") (pinfunction "2_2") (pintype "passive"))
      (node (ref "C18") (pin "1") (pinfunction "1_1") (pintype "passive"))
      (node (ref "C19") (pin "2") (pintype "passive"))
      (node (ref "C21") (pin "2") (pinfunction "2_2") (pintype "passive"))
      (node (ref "C22") (pin "2") (pinfunction "2_2") (pintype "passive"))
      (node (ref "C24") (pin "2") (pintype "passive"))
      (node (ref "C25") (pin "2") (pintype "passive"))
      (node (ref "C26") (pin "2") (pinfunction "2_2") (pintype "passive"))
      (node (ref "C3") (pin "1") (pinfunction "1_1") (pintype "passive"))
      (node (ref "C33") (pin "2") (pinfunction "2_2") (pintype "passive"))
      (node (ref "C34") (pin "2") (pinfunction "2_2") (pintype "passive"))
      (node (ref "C35") (pin "2") (pinfunction "2_2") (pintype "passive"))
      (node (ref "C4") (pin "1") (pinfunction "1_1") (pintype "passive"))
      (node (ref "C40") (pin "2") (pinfunction "2_2") (pintype "passive"))
      (node (ref "C41") (pin "2") (pinfunction "2_2") (pintype "passive"))
      (node (ref "C42") (pin "2") (pinfunction "2_2") (pintype "passive"))
      (node (ref "C44") (pin "2") (pinfunction "2_2") (pintype "passive"))
      (node (ref "C6") (pin "2") (pintype "passive"))
      (node (ref "C7") (pin "1") (pinfunction "1_1") (pintype "passive"))
      (node (ref "C8") (pin "2") (pintype "passive"))
      (node (ref "C9") (pin "1") (pinfunction "1_1") (pintype "passive"))
      (node (ref "D2") (pin "2") (pinfunction "2_2") (pintype "passive"))
      (node (ref "D3") (pin "2") (pinfunction "2_2") (pintype "passive"))
      (node (ref "K2") (pin "2") (pinfunction "NO_2") (pintype "passive"))
      (node (ref "P1") (pin "2") (pinfunction "2_2") (pintype "passive"))
      (node (ref "P1") (pin "3") (pinfunction "3_3") (pintype "passive"))
      (node (ref "P14") (pin "3") (pinfunction "3_3") (pintype "passive"))
      (node (ref "P14") (pin "4") (pinfunction "4_4") (pintype "passive"))
      (node (ref "P19") (pin "2") (pintype "passive"))
      (node (ref "P2") (pin "2") (pinfunction "2_2") (pintype "passive"))
      (node (ref "P3") (pin "1") (pinfunction "EP_1") (pintype "passive"))
      (node (ref "P3") (pin "2") (pinfunction "EP_2") (pintype "passive"))
      (node (ref "P3") (pin "3") (pinfunction "EP_3") (pintype "passive"))
      (node (ref "P3") (pin "4") (pinfunction "EP_4") (pintype "passive"))
      (node (ref "P3") (pin "A1") (pinfunction "GND_A1") (pintype "passive"))
      (node (ref "P3") (pin "A12") (pinfunction "GND_A12") (pintype "passive"))
      (node (ref "P3") (pin "B1") (pinfunction "GND_B1") (pintype "passive"))
      (node (ref "P3") (pin "B12") (pinfunction "GND_B12") (pintype "passive"))
      (node (ref "P4") (pin "1") (pinfunction "1_1") (pintype "passive"))
      (node (ref "P5") (pin "2") (pinfunction "2_2") (pintype "passive"))
      (node (ref "P7") (pin "2") (pinfunction "2_2") (pintype "passive"))
      (node (ref "Q1") (pin "3") (pinfunction "E_3") (pintype "passive"))
      (node (ref "Q2") (pin "3") (pinfunction "E_3") (pintype "passive"))
      (node (ref "R13") (pin "1") (pinfunction "1_1") (pintype "passive"))
      (node (ref "R16") (pin "1") (pinfunction "1_1") (pintype "passive"))
      (node (ref "R20") (pin "2") (pinfunction "2_2") (pintype "passive"))
      (node (ref "R21") (pin "1") (pinfunction "1_1") (pintype "passive"))
      (node (ref "R22") (pin "2") (pinfunction "2_2") (pintype "passive"))
      (node (ref "R23") (pin "1") (pinfunction "1_1") (pintype "passive"))
      (node (ref "R25") (pin "1") (pinfunction "1_1") (pintype "passive"))
      (node (ref "R28") (pin "1") (pinfunction "1_1") (pintype "passive"))
      (node (ref "R29") (pin "1") (pinfunction "A_1") (pintype "passive"))
      (node (ref "R30") (pin "1") (pinfunction "A_1") (pintype "passive"))
      (node (ref "R37") (pin "2") (pinfunction "2_2") (pintype "passive"))
      (node (ref "R38") (pin "2") (pinfunction "2_2") (pintype "passive"))
      (node (ref "R39") (pin "2") (pinfunction "2_2") (pintype "passive"))
      (node (ref "R4") (pin "1") (pinfunction "1_1") (pintype "passive"))
      (node (ref "R40") (pin "1") (pinfunction "1_1") (pintype "passive"))
      (node (ref "R42") (pin "1") (pinfunction "A_1") (pintype "passive"))
      (node (ref "R45") (pin "2") (pinfunction "2_2") (pintype "passive"))
      (node (ref "R5") (pin "1") (pinfunction "1_1") (pintype "passive"))
      (node (ref "R7") (pin "1") (pinfunction "1_1") (pintype "passive"))
      (node (ref "U1") (pin "2") (pinfunction "GND_2") (pintype "passive"))
      (node (ref "U10") (pin "3") (pinfunction "GND_3") (pintype "passive"))
      (node (ref "U2") (pin "1") (pinfunction "GND_1") (pintype "power_in"))
      (node (ref "U3") (pin "5") (pinfunction "5_5") (pintype "passive"))
      (node (ref "U4") (pin "23") (pinfunction "VSS_1_23") (pintype "power_in"))
      (node (ref "U4") (pin "35") (pinfunction "VSS_2_35") (pintype "power_in"))
      (node (ref "U4") (pin "47") (pinfunction "VSS_3_47") (pintype "power_in"))
      (node (ref "U4") (pin "8") (pinfunction "VSSA_8") (pintype "power_in"))
      (node (ref "U5") (pin "18") (pinfunction "GND_18") (pintype "passive"))
      (node (ref "U5") (pin "3") (pinfunction "GND_3") (pintype "passive"))
      (node (ref "U6") (pin "18") (pinfunction "GND_18") (pintype "passive"))
      (node (ref "U6") (pin "3") (pinfunction "GND_3") (pintype "passive"))
      (node (ref "U7") (pin "18") (pinfunction "GND_18") (pintype "passive"))
      (node (ref "U7") (pin "3") (pinfunction "GND_3") (pintype "passive"))
      (node (ref "U9") (pin "1") (pinfunction "1_1") (pintype "passive"))
    )
    (net (code "51") (name "Net-(B1--)") (class "Default")
      (node (ref "B1") (pin "2") (pinfunction "-_2") (pintype "passive"))
      (node (ref "Q2") (pin "2") (pinfunction "C_2") (pintype "passive"))
    )
    (net (code "52") (name "Net-(C43-Pad1)") (class "Default")
      (node (ref "C43") (pin "1") (pinfunction "1_1") (pintype "passive"))
      (node (ref "U9") (pin "13") (pinfunction "13_13") (pintype "passive"))
    )
    (net (code "53") (name "Net-(C44-Pad1)") (class "Default")
      (node (ref "C44") (pin "1") (pinfunction "1_1") (pintype "passive"))
      (node (ref "U9") (pin "4") (pinfunction "4_4") (pintype "passive"))
    )
    (net (code "54") (name "Net-(D2-Pad1)") (class "Default")
      (node (ref "D2") (pin "1") (pinfunction "1_1") (pintype "passive"))
      (node (ref "R1") (pin "2") (pinfunction "2_2") (pintype "passive"))
    )
    (net (code "55") (name "Net-(D3-Pad1)") (class "Default")
      (node (ref "D3") (pin "1") (pinfunction "1_1") (pintype "passive"))
      (node (ref "R2") (pin "2") (pinfunction "2_2") (pintype "passive"))
    )
    (net (code "56") (name "Net-(D5-Pad1)") (class "Default")
      (node (ref "D5") (pin "1") (pinfunction "1_1") (pintype "passive"))
      (node (ref "R31") (pin "1") (pinfunction "1_1") (pintype "passive"))
    )
    (net (code "57") (name "Net-(D6-Pad2)") (class "Default")
      (node (ref "D6") (pin "2") (pinfunction "2_2") (pintype "passive"))
      (node (ref "R7") (pin "2") (pinfunction "2_2") (pintype "passive"))
    )
    (net (code "58") (name "Net-(K1-Pad2)") (class "Default")
      (node (ref "K1") (pin "2") (pinfunction "2_2") (pintype "passive"))
      (node (ref "P1") (pin "1") (pinfunction "1_1") (pintype "passive"))
    )
    (net (code "59") (name "Net-(P5-Pad3)") (class "Default")
      (node (ref "P5") (pin "3") (pinfunction "3_3") (pintype "passive"))
      (node (ref "R11") (pin "2") (pinfunction "2_2") (pintype "passive"))
    )
    (net (code "60") (name "Net-(P14-Pad6)") (class "Default")
      (node (ref "P14") (pin "6") (pinfunction "6_6") (pintype "passive"))
      (node (ref "R18") (pin "2") (pinfunction "2_2") (pintype "passive"))
    )
    (net (code "61") (name "Net-(P14-Pad8)") (class "Default")
      (node (ref "P14") (pin "8") (pinfunction "8_8") (pintype "passive"))
      (node (ref "R19") (pin "2") (pinfunction "2_2") (pintype "passive"))
    )
    (net (code "62") (name "Net-(Q1-B)") (class "Default")
      (node (ref "Q1") (pin "1") (pinfunction "B_1") (pintype "passive"))
      (node (ref "R17") (pin "2") (pinfunction "2_2") (pintype "passive"))
      (node (ref "R25") (pin "2") (pinfunction "2_2") (pintype "passive"))
    )
    (net (code "63") (name "Net-(Q1-C)") (class "Default")
      (node (ref "P6") (pin "1") (pintype "passive"))
      (node (ref "Q1") (pin "2") (pinfunction "C_2") (pintype "passive"))
    )
    (net (code "64") (name "Net-(Q2-B)") (class "Default")
      (node (ref "Q2") (pin "1") (pinfunction "B_1") (pintype "passive"))
      (node (ref "R24") (pin "2") (pinfunction "2_2") (pintype "passive"))
      (node (ref "R28") (pin "2") (pinfunction "2_2") (pintype "passive"))
    )
    (net (code "65") (name "Net-(R29-B)") (class "Default")
      (node (ref "R26") (pin "1") (pinfunction "1_1") (pintype "passive"))
      (node (ref "R29") (pin "3") (pinfunction "B_3") (pintype "passive"))
    )
    (net (code "66") (name "Net-(R29-TAP)") (class "Default")
      (node (ref "R29") (pin "2") (pinfunction "TAP_2") (pintype "passive"))
      (node (ref "U5") (pin "17") (pinfunction "REF_17") (pintype "passive"))
    )
    (net (code "67") (name "Net-(R30-B)") (class "Default")
      (node (ref "R27") (pin "1") (pinfunction "1_1") (pintype "passive"))
      (node (ref "R30") (pin "3") (pinfunction "B_3") (pintype "passive"))
    )
    (net (code "68") (name "Net-(R30-TAP)") (class "Default")
      (node (ref "R30") (pin "2") (pinfunction "TAP_2") (pintype "passive"))
      (node (ref "U6") (pin "17") (pinfunction "REF_17") (pintype "passive"))
    )
    (net (code "69") (name "Net-(R42-B)") (class "Default")
      (node (ref "R41") (pin "1") (pinfunction "1_1") (pintype "passive"))
      (node (ref "R42") (pin "3") (pinfunction "B_3") (pintype "passive"))
    )
    (net (code "70") (name "Net-(R42-TAP)") (class "Default")
      (node (ref "R42") (pin "2") (pinfunction "TAP_2") (pintype "passive"))
      (node (ref "U7") (pin "17") (pinfunction "REF_17") (pintype "passive"))
    )
    (net (code "71") (name "Net-(R51-Pad1)") (class "Default")
      (node (ref "R51") (pin "1") (pinfunction "1_1") (pintype "passive"))
      (node (ref "U9") (pin "2") (pinfunction "2_2") (pintype "passive"))
    )
    (net (code "72") (name "Net-(R52-Pad1)") (class "Default")
      (node (ref "R52") (pin "1") (pinfunction "1_1") (pintype "passive"))
      (node (ref "U9") (pin "3") (pinfunction "3_3") (pintype "passive"))
    )
    (net (code "73") (name "Net-(U1-VIN)") (class "Default")
      (node (ref "C4") (pin "2") (pinfunction "2_2") (pintype "passive"))
      (node (ref "C6") (pin "1") (pintype "passive"))
      (node (ref "D1") (pin "2") (pinfunction "2_2") (pintype "passive"))
      (node (ref "U1") (pin "1") (pinfunction "VIN_1") (pintype "passive"))
    )
    (net (code "74") (name "Net-(U4-PC13-TAMPER-RTC)") (class "Default")
      (node (ref "D5") (pin "2") (pinfunction "2_2") (pintype "passive"))
      (node (ref "U4") (pin "2") (pinfunction "PC13-TAMPER-RTC_2") (pintype "bidirectional"))
    )
    (net (code "75") (name "Net-(U5-CP1)") (class "Default")
      (node (ref "C27") (pin "1") (pinfunction "1_1") (pintype "passive"))
      (node (ref "U5") (pin "4") (pinfunction "CP1_4") (pintype "passive"))
    )
    (net (code "76") (name "Net-(U5-CP2)") (class "Default")
      (node (ref "C27") (pin "2") (pinfunction "2_2") (pintype "passive"))
      (node (ref "U5") (pin "5") (pinfunction "CP2_5") (pintype "passive"))
    )
    (net (code "77") (name "Net-(U5-MS1)") (class "Default")
      (node (ref "R35") (pin "2") (pinfunction "2_2") (pintype "passive"))
      (node (ref "U5") (pin "10") (pinfunction "MS2_10") (pintype "passive"))
      (node (ref "U5") (pin "11") (pinfunction "MS3_11") (pintype "passive"))
      (node (ref "U5") (pin "9") (pinfunction "MS1_9") (pintype "passive"))
    )
    (net (code "78") (name "Net-(U5-SENSE1)") (class "Default")
      (node (ref "R21") (pin "2") (pinfunction "2_2") (pintype "passive"))
      (node (ref "U5") (pin "23") (pinfunction "SENSE1_23") (pintype "passive"))
    )
    (net (code "79") (name "Net-(U5-SENSE2)") (class "Default")
      (node (ref "R20") (pin "1") (pinfunction "1_1") (pintype "passive"))
      (node (ref "U5") (pin "27") (pinfunction "SENSE2_27") (pintype "passive"))
    )
    (net (code "80") (name "Net-(U5-VCP)") (class "Default")
      (node (ref "C30") (pin "1") (pinfunction "1_1") (pintype "passive"))
      (node (ref "U5") (pin "6") (pinfunction "VCP_6") (pintype "passive"))
    )
    (net (code "81") (name "Net-(U5-VREG)") (class "Default")
      (node (ref "C33") (pin "1") (pinfunction "1_1") (pintype "passive"))
      (node (ref "U5") (pin "8") (pinfunction "VREG_8") (pintype "passive"))
    )
    (net (code "82") (name "Net-(U5-~{RESET})") (class "Default")
      (node (ref "R32") (pin "2") (pinfunction "2_2") (pintype "passive"))
      (node (ref "U5") (pin "12") (pinfunction "~{RESET}_12") (pintype "passive"))
      (node (ref "U5") (pin "14") (pinfunction "~{SLEEP}_14") (pintype "passive"))
    )
    (net (code "83") (name "Net-(U5-~{ROSC})") (class "Default")
      (node (ref "R38") (pin "1") (pinfunction "1_1") (pintype "passive"))
      (node (ref "U5") (pin "13") (pinfunction "~{ROSC}_13") (pintype "passive"))
    )
    (net (code "84") (name "Net-(U6-CP1)") (class "Default")
      (node (ref "C28") (pin "1") (pinfunction "1_1") (pintype "passive"))
      (node (ref "U6") (pin "4") (pinfunction "CP1_4") (pintype "passive"))
    )
    (net (code "85") (name "Net-(U6-CP2)") (class "Default")
      (node (ref "C28") (pin "2") (pinfunction "2_2") (pintype "passive"))
      (node (ref "U6") (pin "5") (pinfunction "CP2_5") (pintype "passive"))
    )
    (net (code "86") (name "Net-(U6-MS1)") (class "Default")
      (node (ref "R36") (pin "2") (pinfunction "2_2") (pintype "passive"))
      (node (ref "U6") (pin "10") (pinfunction "MS2_10") (pintype "passive"))
      (node (ref "U6") (pin "11") (pinfunction "MS3_11") (pintype "passive"))
      (node (ref "U6") (pin "9") (pinfunction "MS1_9") (pintype "passive"))
    )
    (net (code "87") (name "Net-(U6-SENSE1)") (class "Default")
      (node (ref "R23") (pin "2") (pinfunction "2_2") (pintype "passive"))
      (node (ref "U6") (pin "23") (pinfunction "SENSE1_23") (pintype "passive"))
    )
    (net (code "88") (name "Net-(U6-SENSE2)") (class "Default")
      (node (ref "R22") (pin "1") (pinfunction "1_1") (pintype "passive"))
      (node (ref "U6") (pin "27") (pinfunction "SENSE2_27") (pintype "passive"))
    )
    (net (code "89") (name "Net-(U6-VCP)") (class "Default")
      (node (ref "C31") (pin "1") (pinfunction "1_1") (pintype "passive"))
      (node (ref "U6") (pin "6") (pinfunction "VCP_6") (pintype "passive"))
    )
    (net (code "90") (name "Net-(U6-VREG)") (class "Default")
      (node (ref "C34") (pin "1") (pinfunction "1_1") (pintype "passive"))
      (node (ref "U6") (pin "8") (pinfunction "VREG_8") (pintype "passive"))
    )
    (net (code "91") (name "Net-(U6-~{RESET})") (class "Default")
      (node (ref "R33") (pin "2") (pinfunction "2_2") (pintype "passive"))
      (node (ref "U6") (pin "12") (pinfunction "~{RESET}_12") (pintype "passive"))
      (node (ref "U6") (pin "14") (pinfunction "~{SLEEP}_14") (pintype "passive"))
    )
    (net (code "92") (name "Net-(U6-~{ROSC})") (class "Default")
      (node (ref "R39") (pin "1") (pinfunction "1_1") (pintype "passive"))
      (node (ref "U6") (pin "13") (pinfunction "~{ROSC}_13") (pintype "passive"))
    )
    (net (code "93") (name "Net-(U7-CP1)") (class "Default")
      (node (ref "C20") (pin "1") (pinfunction "1_1") (pintype "passive"))
      (node (ref "U7") (pin "4") (pinfunction "CP1_4") (pintype "passive"))
    )
    (net (code "94") (name "Net-(U7-CP2)") (class "Default")
      (node (ref "C20") (pin "2") (pinfunction "2_2") (pintype "passive"))
      (node (ref "U7") (pin "5") (pinfunction "CP2_5") (pintype "passive"))
    )
    (net (code "95") (name "Net-(U7-MS1)") (class "Default")
      (node (ref "R44") (pin "2") (pinfunction "2_2") (pintype "passive"))
      (node (ref "U7") (pin "10") (pinfunction "MS2_10") (pintype "passive"))
      (node (ref "U7") (pin "11") (pinfunction "MS3_11") (pintype "passive"))
      (node (ref "U7") (pin "9") (pinfunction "MS1_9") (pintype "passive"))
    )
    (net (code "96") (name "Net-(U7-SENSE1)") (class "Default")
      (node (ref "R40") (pin "2") (pinfunction "2_2") (pintype "passive"))
      (node (ref "U7") (pin "23") (pinfunction "SENSE1_23") (pintype "passive"))
    )
    (net (code "97") (name "Net-(U7-SENSE2)") (class "Default")
      (node (ref "R37") (pin "1") (pinfunction "1_1") (pintype "passive"))
      (node (ref "U7") (pin "27") (pinfunction "SENSE2_27") (pintype "passive"))
    )
    (net (code "98") (name "Net-(U7-VCP)") (class "Default")
      (node (ref "C23") (pin "1") (pinfunction "1_1") (pintype "passive"))
      (node (ref "U7") (pin "6") (pinfunction "VCP_6") (pintype "passive"))
    )
    (net (code "99") (name "Net-(U7-VREG)") (class "Default")
      (node (ref "C26") (pin "1") (pinfunction "1_1") (pintype "passive"))
      (node (ref "U7") (pin "8") (pinfunction "VREG_8") (pintype "passive"))
    )
    (net (code "100") (name "Net-(U7-~{RESET})") (class "Default")
      (node (ref "R43") (pin "2") (pinfunction "2_2") (pintype "passive"))
      (node (ref "U7") (pin "12") (pinfunction "~{RESET}_12") (pintype "passive"))
      (node (ref "U7") (pin "14") (pinfunction "~{SLEEP}_14") (pintype "passive"))
    )
    (net (code "101") (name "Net-(U7-~{ROSC})") (class "Default")
      (node (ref "R45") (pin "1") (pinfunction "1_1") (pintype "passive"))
      (node (ref "U7") (pin "13") (pinfunction "~{ROSC}_13") (pintype "passive"))
    )
    (net (code "102") (name "Net-(U10-Y)") (class "Default")
      (node (ref "R11") (pin "1") (pinfunction "1_1") (pintype "passive"))
      (node (ref "U10") (pin "4") (pinfunction "Y_4") (pintype "passive"))
    )
    (net (code "103") (name "Net-(Y2-OSC1)") (class "Default")
      (node (ref "C41") (pin "1") (pinfunction "1_1") (pintype "passive"))
      (node (ref "U9") (pin "8") (pinfunction "8_8") (pintype "passive"))
      (node (ref "Y2") (pin "1") (pinfunction "OSC1_1") (pintype "passive"))
    )
    (net (code "104") (name "Net-(Y2-OSC2)") (class "Default")
      (node (ref "C40") (pin "1") (pinfunction "1_1") (pintype "passive"))
      (node (ref "U9") (pin "7") (pinfunction "7_7") (pintype "passive"))
      (node (ref "Y2") (pin "2") (pinfunction "OSC2_2") (pintype "passive"))
    )
    (net (code "105") (name "USBV_CK") (class "Default")
      (node (ref "R15") (pin "1") (pinfunction "1_1") (pintype "passive"))
      (node (ref "R16") (pin "2") (pinfunction "2_2") (pintype "passive"))
      (node (ref "U4") (pin "18") (pinfunction "PB0_18") (pintype "bidirectional"))
    )
    (net (code "106") (name "VCC") (class "Default")
      (node (ref "B1") (pin "1") (pinfunction "+_1") (pintype "passive"))
      (node (ref "C1") (pin "1") (pintype "passive"))
      (node (ref "C13") (pin "2") (pinfunction "2_2") (pintype "passive"))
      (node (ref "C3") (pin "2") (pinfunction "2_2") (pintype "passive"))
      (node (ref "D4") (pin "2") (pinfunction "2_2") (pintype "passive"))
      (node (ref "P14") (pin "1") (pinfunction "1_1") (pintype "passive"))
      (node (ref "P14") (pin "2") (pinfunction "2_2") (pintype "passive"))
      (node (ref "P2") (pin "3") (pinfunction "3_3") (pintype "passive"))
      (node (ref "P6") (pin "2") (pintype "passive"))
      (node (ref "P7") (pin "3") (pinfunction "3_3") (pintype "passive"))
      (node (ref "R1") (pin "1") (pinfunction "1_1") (pintype "passive"))
      (node (ref "R12") (pin "2") (pinfunction "2_2") (pintype "passive"))
      (node (ref "R26") (pin "2") (pinfunction "2_2") (pintype "passive"))
      (node (ref "R27") (pin "2") (pinfunction "2_2") (pintype "passive"))
      (node (ref "R3") (pin "2") (pinfunction "2_2") (pintype "passive"))
      (node (ref "R32") (pin "1") (pinfunction "1_1") (pintype "passive"))
      (node (ref "R33") (pin "1") (pinfunction "1_1") (pintype "passive"))
      (node (ref "R35") (pin "1") (pinfunction "1_1") (pintype "passive"))
      (node (ref "R36") (pin "1") (pinfunction "1_1") (pintype "passive"))
      (node (ref "R41") (pin "2") (pinfunction "2_2") (pintype "passive"))
      (node (ref "R43") (pin "1") (pinfunction "1_1") (pintype "passive"))
      (node (ref "R44") (pin "1") (pinfunction "1_1") (pintype "passive"))
      (node (ref "U1") (pin "3") (pinfunction "VOUT_3") (pintype "passive"))
      (node (ref "U10") (pin "5") (pinfunction "VCC_5") (pintype "passive"))
      (node (ref "U2") (pin "3") (pinfunction "IN_3") (pintype "power_in"))
      (node (ref "U5") (pin "15") (pinfunction "VDD_15") (pintype "passive"))
      (node (ref "U6") (pin "15") (pinfunction "VDD_15") (pintype "passive"))
      (node (ref "U7") (pin "15") (pinfunction "VDD_15") (pintype "passive"))
    )
    (net (code "107") (name "VUSB") (class "Default")
      (node (ref "C42") (pin "1") (pinfunction "1_1") (pintype "passive"))
      (node (ref "D4") (pin "1") (pinfunction "1_1") (pintype "passive"))
      (node (ref "D6") (pin "1") (pinfunction "1_1") (pintype "passive"))
      (node (ref "P3") (pin "A4") (pinfunction "VBUS_A4") (pintype "passive"))
      (node (ref "P3") (pin "A9") (pinfunction "VBUS_A9") (pintype "passive"))
      (node (ref "P3") (pin "B4") (pinfunction "VBUS_B4") (pintype "passive"))
      (node (ref "P3") (pin "B9") (pinfunction "VBUS_B9") (pintype "passive"))
      (node (ref "R15") (pin "2") (pinfunction "2_2") (pintype "passive"))
      (node (ref "U9") (pin "16") (pinfunction "16_16") (pintype "passive"))
    )
    (net (code "108") (name "unconnected-(P3-CC1-PadA5)") (class "Default")
      (node (ref "P3") (pin "A5") (pinfunction "CC1_A5") (pintype "passive"))
    )
    (net (code "109") (name "unconnected-(P3-CC2-PadB5)") (class "Default")
      (node (ref "P3") (pin "B5") (pinfunction "CC2_B5") (pintype "passive"))
    )
    (net (code "110") (name "unconnected-(P3-SUB1-PadA8)") (class "Default")
      (node (ref "P3") (pin "A8") (pinfunction "SUB1_A8") (pintype "passive"))
    )
    (net (code "111") (name "unconnected-(P3-SUB2-PadB8)") (class "Default")
      (node (ref "P3") (pin "B8") (pinfunction "SUB2_B8") (pintype "passive"))
    )
    (net (code "112") (name "unconnected-(P14-Pad7)") (class "Default")
      (node (ref "P14") (pin "7") (pinfunction "7_7") (pintype "passive"))
    )
    (net (code "113") (name "unconnected-(U3-Pad1)") (class "Default")
      (node (ref "U3") (pin "1") (pinfunction "1_1") (pintype "passive"))
    )
    (net (code "114") (name "unconnected-(U3-Pad6)") (class "Default")
      (node (ref "U3") (pin "6") (pinfunction "6_6") (pintype "passive"))
    )
    (net (code "115") (name "unconnected-(U3-Pad7)") (class "Default")
      (node (ref "U3") (pin "7") (pinfunction "7_7") (pintype "passive"))
    )
    (net (code "116") (name "unconnected-(U3-Pad8)") (class "Default")
      (node (ref "U3") (pin "8") (pinfunction "8_8") (pintype "passive"))
    )
    (net (code "117") (name "unconnected-(U3-Pad9)") (class "Default")
      (node (ref "U3") (pin "9") (pinfunction "9_9") (pintype "passive"))
    )
    (net (code "118") (name "unconnected-(U3-Pad10)") (class "Default")
      (node (ref "U3") (pin "10") (pinfunction "10_10") (pintype "passive"))
    )
    (net (code "119") (name "unconnected-(U3-Pad11)") (class "Default")
      (node (ref "U3") (pin "11") (pinfunction "11_11") (pintype "passive"))
    )
    (net (code "120") (name "unconnected-(U3-Pad12)") (class "Default")
      (node (ref "U3") (pin "12") (pinfunction "12_12") (pintype "passive"))
    )
    (net (code "121") (name "unconnected-(U4-PA11-Pad32)") (class "Default")
      (node (ref "U4") (pin "32") (pinfunction "PA11_32") (pintype "bidirectional"))
    )
    (net (code "122") (name "unconnected-(U4-PA12-Pad33)") (class "Default")
      (node (ref "U4") (pin "33") (pinfunction "PA12_33") (pintype "bidirectional"))
    )
    (net (code "123") (name "unconnected-(U4-PC14-OSC32_IN-Pad3)") (class "Default")
      (node (ref "U4") (pin "3") (pinfunction "PC14-OSC32_IN_3") (pintype "bidirectional"))
    )
    (net (code "124") (name "unconnected-(U4-PC15-OSC32_OUT-Pad4)") (class "Default")
      (node (ref "U4") (pin "4") (pinfunction "PC15-OSC32_OUT_4") (pintype "bidirectional"))
    )
    (net (code "125") (name "unconnected-(U4-VBAT-Pad1)") (class "Default")
      (node (ref "U4") (pin "1") (pinfunction "VBAT_1") (pintype "power_in"))
    )
    (net (code "126") (name "unconnected-(U5-NC-Pad7)") (class "Default")
      (node (ref "U5") (pin "7") (pinfunction "NC_7") (pintype "passive"))
    )
    (net (code "127") (name "unconnected-(U5-NC-Pad20)") (class "Default")
      (node (ref "U5") (pin "20") (pinfunction "NC_20") (pintype "passive"))
    )
    (net (code "128") (name "unconnected-(U5-NC-Pad25)") (class "Default")
      (node (ref "U5") (pin "25") (pinfunction "NC_25") (pintype "passive"))
    )
    (net (code "129") (name "unconnected-(U6-NC-Pad7)") (class "Default")
      (node (ref "U6") (pin "7") (pinfunction "NC_7") (pintype "passive"))
    )
    (net (code "130") (name "unconnected-(U6-NC-Pad20)") (class "Default")
      (node (ref "U6") (pin "20") (pinfunction "NC_20") (pintype "passive"))
    )
    (net (code "131") (name "unconnected-(U6-NC-Pad25)") (class "Default")
      (node (ref "U6") (pin "25") (pinfunction "NC_25") (pintype "passive"))
    )
    (net (code "132") (name "unconnected-(U7-NC-Pad7)") (class "Default")
      (node (ref "U7") (pin "7") (pinfunction "NC_7") (pintype "passive"))
    )
    (net (code "133") (name "unconnected-(U7-NC-Pad20)") (class "Default")
      (node (ref "U7") (pin "20") (pinfunction "NC_20") (pintype "passive"))
    )
    (net (code "134") (name "unconnected-(U7-NC-Pad25)") (class "Default")
      (node (ref "U7") (pin "25") (pinfunction "NC_25") (pintype "passive"))
    )
    (net (code "135") (name "unconnected-(U9-Pad9)") (class "Default")
      (node (ref "U9") (pin "9") (pinfunction "9_9") (pintype "passive"))
    )
    (net (code "136") (name "unconnected-(U9-Pad10)") (class "Default")
      (node (ref "U9") (pin "10") (pinfunction "10_10") (pintype "passive"))
    )
    (net (code "137") (name "unconnected-(U9-Pad11)") (class "Default")
      (node (ref "U9") (pin "11") (pinfunction "11_11") (pintype "passive"))
    )
    (net (code "138") (name "unconnected-(U9-Pad12)") (class "Default")
      (node (ref "U9") (pin "12") (pinfunction "12_12") (pintype "passive"))
    )
    (net (code "139") (name "unconnected-(U9-Pad14)") (class "Default")
      (node (ref "U9") (pin "14") (pinfunction "14_14") (pintype "passive"))
    )
    (net (code "140") (name "unconnected-(U9-Pad15)") (class "Default")
      (node (ref "U9") (pin "15") (pinfunction "15_15") (pintype "passive"))
    )
    (net (code "141") (name "unconnected-(U10-NC-Pad1)") (class "Default")
      (node (ref "U10") (pin "1") (pinfunction "NC_1") (pintype "passive"))
    )
  )
)
